# bandido.net
KiCad netlist of a schematic drawn in EAGLE
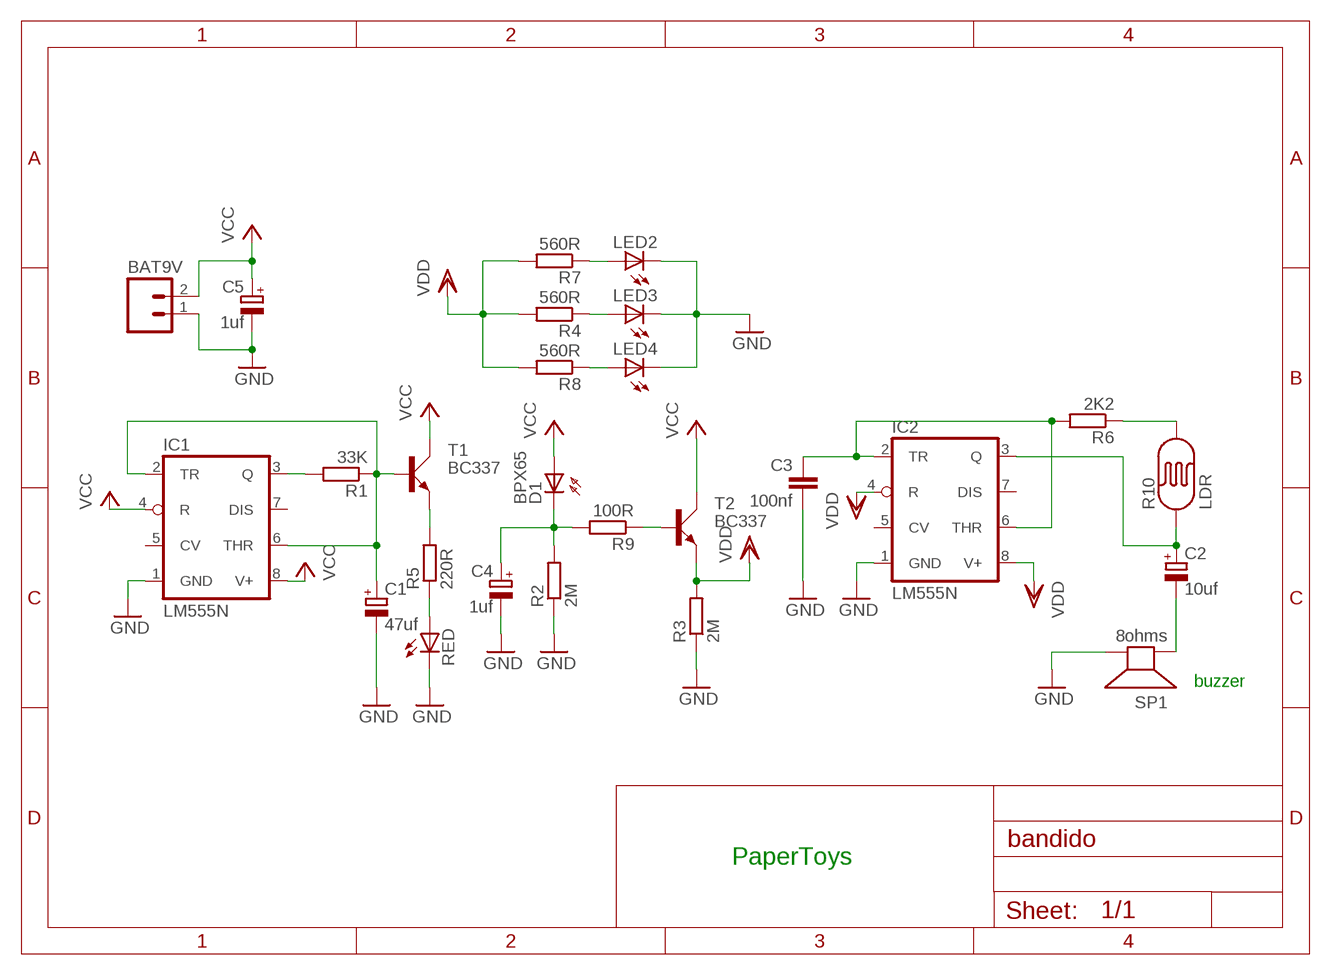
[diagram p0: schematic, sheet 1]

(export (version "E")
  (design (tool "Eeschema 10.0.6"))
  (components
    (comp (ref "BAT9V")
      (value "M025MM")
      (footprint "eagle-import:SCREWTERMINAL-5MM-2")
      (libsource (lib "eagle-import") (part "M025MM"))
    )
    (comp (ref "C1")
      (value "47uf")
      (footprint "eagle-import:E5-4")
      (libsource (lib "eagle-import") (part "CPOL-EUE5-4"))
    )
    (comp (ref "C2")
      (value "10uf")
      (footprint "eagle-import:E5-4")
      (libsource (lib "eagle-import") (part "CPOL-EUE5-4"))
    )
    (comp (ref "C3")
      (value "100nf")
      (footprint "eagle-import:C025-024X044")
      (libsource (lib "eagle-import") (part "C-EU025-024X044"))
    )
    (comp (ref "C4")
      (value "1uf")
      (footprint "eagle-import:E5-4")
      (libsource (lib "eagle-import") (part "CPOL-EUE5-4"))
    )
    (comp (ref "C5")
      (value "1uf")
      (footprint "eagle-import:E5-4")
      (libsource (lib "eagle-import") (part "CPOL-EUE5-4"))
    )
    (comp (ref "D1")
      (value "BPX65")
      (footprint "eagle-import:BPX65")
      (fields (field (name "MPN") "BPX65."))
      (libsource (lib "eagle-import") (part "BPX65"))
    )
    (comp (ref "IC1")
      (value "LM555N")
      (footprint "eagle-import:DIL08-ROUND")
      (libsource (lib "eagle-import") (part "555NLM"))
    )
    (comp (ref "IC2")
      (value "LM555N")
      (footprint "eagle-import:DIL08-ROUND")
      (libsource (lib "eagle-import") (part "555NLM"))
    )
    (comp (ref "LED2")
      (value "LED5MM")
      (footprint "eagle-import:LED5MM")
      (libsource (lib "eagle-import") (part "LED5MM"))
    )
    (comp (ref "LED3")
      (value "LED5MM")
      (footprint "eagle-import:LED5MM")
      (libsource (lib "eagle-import") (part "LED5MM"))
    )
    (comp (ref "LED4")
      (value "LED5MM")
      (footprint "eagle-import:LED5MM")
      (libsource (lib "eagle-import") (part "LED5MM"))
    )
    (comp (ref "R1")
      (value "33K")
      (footprint "eagle-import:0204_7")
      (libsource (lib "eagle-import") (part "R-EU_0204/7"))
    )
    (comp (ref "R2")
      (value "2M")
      (footprint "eagle-import:0204_7")
      (libsource (lib "eagle-import") (part "R-EU_0204/7"))
    )
    (comp (ref "R3")
      (value "2M")
      (footprint "eagle-import:0204_7")
      (libsource (lib "eagle-import") (part "R-EU_0204/7"))
    )
    (comp (ref "R4")
      (value "560R")
      (footprint "eagle-import:0204_7")
      (libsource (lib "eagle-import") (part "R-EU_0204/7"))
    )
    (comp (ref "R5")
      (value "220R")
      (footprint "eagle-import:0204_7")
      (libsource (lib "eagle-import") (part "R-EU_0204/7"))
    )
    (comp (ref "R6")
      (value "2K2")
      (footprint "eagle-import:0204_7")
      (libsource (lib "eagle-import") (part "R-EU_0204/7"))
    )
    (comp (ref "R7")
      (value "560R")
      (footprint "eagle-import:0204_7")
      (libsource (lib "eagle-import") (part "R-EU_0204/7"))
    )
    (comp (ref "R8")
      (value "560R")
      (footprint "eagle-import:0204_7")
      (libsource (lib "eagle-import") (part "R-EU_0204/7"))
    )
    (comp (ref "R9")
      (value "100R")
      (footprint "eagle-import:0204_7")
      (libsource (lib "eagle-import") (part "R-EU_0204/7"))
    )
    (comp (ref "R10")
      (value "LDR")
      (footprint "eagle-import:PHOTOCELL-KIT")
      (libsource (lib "eagle-import") (part "PHOTOCELLPTH-KIT"))
    )
    (comp (ref "RED")
      (value "LED5MM")
      (footprint "eagle-import:LED5MM")
      (libsource (lib "eagle-import") (part "LED5MM"))
    )
    (comp (ref "SP1")
      (value "8ohms")
      (footprint "eagle-import:AL11P")
      (libsource (lib "eagle-import") (part "SPEAKER/AL11P"))
    )
    (comp (ref "T1")
      (value "BC337")
      (footprint "eagle-import:SOT54A")
      (libsource (lib "eagle-import") (part "BC337"))
    )
    (comp (ref "T2")
      (value "BC337")
      (footprint "eagle-import:SOT54A")
      (libsource (lib "eagle-import") (part "BC337"))
    )
  )
  (nets
    (net (code "1") (name "GND") (class "Default")
      (node (ref "BAT9V") (pin "1") (pinfunction "1_1") (pintype "passive"))
      (node (ref "C1") (pin "-") (pinfunction "-_-") (pintype "passive"))
      (node (ref "C3") (pin "2") (pinfunction "2_2") (pintype "passive"))
      (node (ref "C4") (pin "-") (pinfunction "-_-") (pintype "passive"))
      (node (ref "C5") (pin "-") (pinfunction "-_-") (pintype "passive"))
      (node (ref "IC1") (pin "1") (pinfunction "GND_1") (pintype "power_in"))
      (node (ref "IC2") (pin "1") (pinfunction "GND_1") (pintype "power_in"))
      (node (ref "LED2") (pin "K") (pinfunction "C_K") (pintype "passive"))
      (node (ref "LED3") (pin "K") (pinfunction "C_K") (pintype "passive"))
      (node (ref "LED4") (pin "K") (pinfunction "C_K") (pintype "passive"))
      (node (ref "R2") (pin "1") (pinfunction "1_1") (pintype "passive"))
      (node (ref "R3") (pin "1") (pinfunction "1_1") (pintype "passive"))
      (node (ref "RED") (pin "K") (pinfunction "C_K") (pintype "passive"))
      (node (ref "SP1") (pin "-") (pinfunction "-_-") (pintype "passive"))
    )
    (net (code "2") (name "Net-(C2-Pad-)") (class "Default")
      (node (ref "C2") (pin "-") (pinfunction "-_-") (pintype "passive"))
      (node (ref "SP1") (pin "+") (pinfunction "+_+") (pintype "passive"))
    )
    (net (code "3") (name "Net-(D1-C)") (class "Default")
      (node (ref "C4") (pin "+") (pinfunction "+_+") (pintype "passive"))
      (node (ref "D1") (pin "K") (pinfunction "C_K") (pintype "passive"))
      (node (ref "R2") (pin "2") (pinfunction "2_2") (pintype "passive"))
      (node (ref "R9") (pin "2") (pinfunction "2_2") (pintype "passive"))
    )
    (net (code "4") (name "Net-(IC1-Q)") (class "Default")
      (node (ref "IC1") (pin "3") (pinfunction "Q_3") (pintype "output"))
      (node (ref "R1") (pin "2") (pinfunction "2_2") (pintype "passive"))
    )
    (net (code "5") (name "Net-(IC1-THR)") (class "Default")
      (node (ref "C1") (pin "+") (pinfunction "+_+") (pintype "passive"))
      (node (ref "IC1") (pin "2") (pinfunction "TR_2") (pintype "input"))
      (node (ref "IC1") (pin "6") (pinfunction "THR_6") (pintype "input"))
      (node (ref "R1") (pin "1") (pinfunction "1_1") (pintype "passive"))
      (node (ref "T1") (pin "B") (pinfunction "B_B") (pintype "passive"))
    )
    (net (code "6") (name "Net-(IC2-Q)") (class "Default")
      (node (ref "C2") (pin "+") (pinfunction "+_+") (pintype "passive"))
      (node (ref "IC2") (pin "3") (pinfunction "Q_3") (pintype "output"))
      (node (ref "R10") (pin "1") (pinfunction "P$1_1") (pintype "bidirectional"))
    )
    (net (code "7") (name "Net-(IC2-THR)") (class "Default")
      (node (ref "C3") (pin "1") (pinfunction "1_1") (pintype "passive"))
      (node (ref "IC2") (pin "2") (pinfunction "TR_2") (pintype "input"))
      (node (ref "IC2") (pin "6") (pinfunction "THR_6") (pintype "input"))
      (node (ref "R6") (pin "2") (pinfunction "2_2") (pintype "passive"))
    )
    (net (code "8") (name "Net-(LED2-PadA)") (class "Default")
      (node (ref "LED2") (pin "A") (pinfunction "A_A") (pintype "passive"))
      (node (ref "R7") (pin "1") (pinfunction "1_1") (pintype "passive"))
    )
    (net (code "9") (name "Net-(LED3-PadA)") (class "Default")
      (node (ref "LED3") (pin "A") (pinfunction "A_A") (pintype "passive"))
      (node (ref "R4") (pin "1") (pinfunction "1_1") (pintype "passive"))
    )
    (net (code "10") (name "Net-(LED4-PadA)") (class "Default")
      (node (ref "LED4") (pin "A") (pinfunction "A_A") (pintype "passive"))
      (node (ref "R8") (pin "1") (pinfunction "1_1") (pintype "passive"))
    )
    (net (code "11") (name "Net-(R5-Pad1)") (class "Default")
      (node (ref "R5") (pin "1") (pinfunction "1_1") (pintype "passive"))
      (node (ref "RED") (pin "A") (pinfunction "A_A") (pintype "passive"))
    )
    (net (code "12") (name "Net-(R5-Pad2)") (class "Default")
      (node (ref "R5") (pin "2") (pinfunction "2_2") (pintype "passive"))
      (node (ref "T1") (pin "E") (pinfunction "E_E") (pintype "passive"))
    )
    (net (code "13") (name "Net-(R9-Pad1)") (class "Default")
      (node (ref "R9") (pin "1") (pinfunction "1_1") (pintype "passive"))
      (node (ref "T2") (pin "B") (pinfunction "B_B") (pintype "passive"))
    )
    (net (code "14") (name "Net-(R10-P$2)") (class "Default")
      (node (ref "R10") (pin "2") (pinfunction "P$2_2") (pintype "bidirectional"))
      (node (ref "R6") (pin "1") (pinfunction "1_1") (pintype "passive"))
    )
    (net (code "15") (name "VCC") (class "Default")
      (node (ref "BAT9V") (pin "2") (pinfunction "2_2") (pintype "passive"))
      (node (ref "C5") (pin "+") (pinfunction "+_+") (pintype "passive"))
      (node (ref "D1") (pin "A") (pinfunction "A_A") (pintype "passive"))
      (node (ref "IC1") (pin "4") (pinfunction "R_4") (pintype "input"))
      (node (ref "IC1") (pin "8") (pinfunction "V+_8") (pintype "power_in"))
      (node (ref "T1") (pin "C") (pinfunction "C_C") (pintype "passive"))
      (node (ref "T2") (pin "C") (pinfunction "C_C") (pintype "passive"))
    )
    (net (code "16") (name "VDD") (class "Default")
      (node (ref "IC2") (pin "4") (pinfunction "R_4") (pintype "input"))
      (node (ref "IC2") (pin "8") (pinfunction "V+_8") (pintype "power_in"))
      (node (ref "R3") (pin "2") (pinfunction "2_2") (pintype "passive"))
      (node (ref "R4") (pin "2") (pinfunction "2_2") (pintype "passive"))
      (node (ref "R7") (pin "2") (pinfunction "2_2") (pintype "passive"))
      (node (ref "R8") (pin "2") (pinfunction "2_2") (pintype "passive"))
      (node (ref "T2") (pin "E") (pinfunction "E_E") (pintype "passive"))
    )
    (net (code "17") (name "unconnected-(IC1-CV-Pad5)") (class "Default")
      (node (ref "IC1") (pin "5") (pinfunction "CV_5") (pintype "input"))
    )
    (net (code "18") (name "unconnected-(IC1-DIS-Pad7)") (class "Default")
      (node (ref "IC1") (pin "7") (pinfunction "DIS_7") (pintype "input"))
    )
    (net (code "19") (name "unconnected-(IC2-CV-Pad5)") (class "Default")
      (node (ref "IC2") (pin "5") (pinfunction "CV_5") (pintype "input"))
    )
    (net (code "20") (name "unconnected-(IC2-DIS-Pad7)") (class "Default")
      (node (ref "IC2") (pin "7") (pinfunction "DIS_7") (pintype "input"))
    )
  )
)
